# Stroya_Stompbox.net
KiCad netlist of a schematic drawn in EAGLE
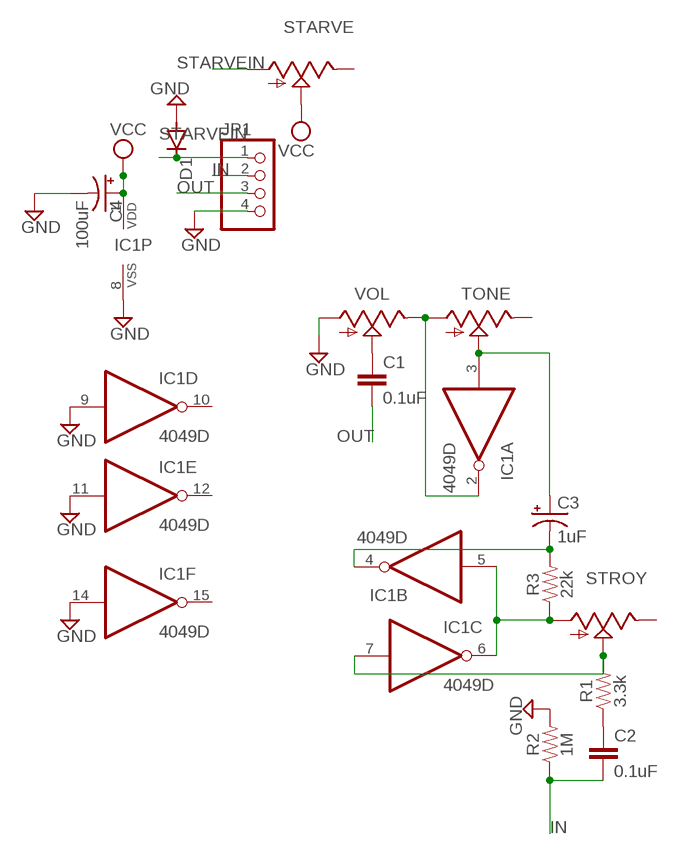
[diagram p0: schematic, sheet 1]

(export (version "E")
  (design (tool "Eeschema 10.0.6"))
  (components
    (comp (ref "C1")
      (value "0.1uF")
      (footprint "eagle-import:0603")
      (libsource (lib "eagle-import") (part "0.1UF-0603-25V-5%"))
    )
    (comp (ref "C2")
      (value "0.1uF")
      (footprint "eagle-import:0603")
      (libsource (lib "eagle-import") (part "0.1UF-0603-25V-5%"))
    )
    (comp (ref "C3")
      (value "1uF")
      (footprint "eagle-import:PAN_B_SMD+THRU")
      (libsource (lib "eagle-import") (part "CAP_SMD+THRUPAN_B"))
    )
    (comp (ref "C4")
      (value "100uF")
      (footprint "eagle-import:PAN_B_SMD+THRU")
      (libsource (lib "eagle-import") (part "CAP_SMD+THRUPAN_B"))
    )
    (comp (ref "D1")
      (value "DIODE-SOD123")
      (footprint "eagle-import:SOD123")
      (libsource (lib "eagle-import") (part "DIODE-SOD123"))
    )
    (comp (ref "IC1")
      (value "4049D")
      (footprint "eagle-import:SO16")
      (libsource (lib "eagle-import") (part "4049D"))
    )
    (comp (ref "JP1")
      (value "PINHD-1X4")
      (footprint "eagle-import:1X04")
      (libsource (lib "eagle-import") (part "PINHD-1X4"))
    )
    (comp (ref "R1")
      (value "3.3k")
      (footprint "eagle-import:0603")
      (libsource (lib "eagle-import") (part "3.3KOHM-0603-1/10W-1%"))
    )
    (comp (ref "R2")
      (value "1M")
      (footprint "eagle-import:0603")
      (libsource (lib "eagle-import") (part "1MOHM-0603-1/4W-5%"))
    )
    (comp (ref "R3")
      (value "22k")
      (footprint "eagle-import:0603")
      (libsource (lib "eagle-import") (part "22KOHM-0603-1/10W-1%"))
    )
    (comp (ref "STARVE")
      (value "9MM_SNAP-IN_POT_")
      (footprint "eagle-import:9MM_SNAP-IN_POT")
      (libsource (lib "eagle-import") (part "9MM_SNAP-IN_POT_"))
    )
    (comp (ref "STROY")
      (value "9MM_SNAP-IN_POT_")
      (footprint "eagle-import:9MM_SNAP-IN_POT")
      (libsource (lib "eagle-import") (part "9MM_SNAP-IN_POT_"))
    )
    (comp (ref "TONE")
      (value "9MM_SNAP-IN_POT_")
      (footprint "eagle-import:9MM_SNAP-IN_POT")
      (libsource (lib "eagle-import") (part "9MM_SNAP-IN_POT_"))
    )
    (comp (ref "VOL")
      (value "9MM_SNAP-IN_POT_")
      (footprint "eagle-import:9MM_SNAP-IN_POT")
      (libsource (lib "eagle-import") (part "9MM_SNAP-IN_POT_"))
    )
  )
  (nets
    (net (code "1") (name "/IN") (class "Default")
      (node (ref "C2") (pin "2") (pinfunction "2_2") (pintype "passive"))
      (node (ref "JP1") (pin "2") (pinfunction "2_2") (pintype "passive"))
      (node (ref "R2") (pin "1") (pinfunction "1_1") (pintype "passive"))
    )
    (net (code "2") (name "/OUT") (class "Default")
      (node (ref "C1") (pin "2") (pinfunction "2_2") (pintype "passive"))
      (node (ref "JP1") (pin "3") (pinfunction "3_3") (pintype "passive"))
    )
    (net (code "3") (name "/STARVEIN") (class "Default")
      (node (ref "D1") (pin "C") (pinfunction "C_C") (pintype "passive"))
      (node (ref "JP1") (pin "1") (pinfunction "1_1") (pintype "passive"))
      (node (ref "STARVE") (pin "1") (pinfunction "A_1") (pintype "passive"))
    )
    (net (code "4") (name "GND") (class "Default")
      (node (ref "C4") (pin "-") (pinfunction "-_-") (pintype "passive"))
      (node (ref "C4") (pin "--") (pinfunction "-_--") (pintype "passive"))
      (node (ref "D1") (pin "A") (pinfunction "A_A") (pintype "passive"))
      (node (ref "IC1") (pin "11") (pinfunction "I_11") (pintype "input"))
      (node (ref "IC1") (pin "14") (pinfunction "I_14") (pintype "input"))
      (node (ref "IC1") (pin "8") (pinfunction "VSS_8") (pintype "power_in"))
      (node (ref "IC1") (pin "9") (pinfunction "I_9") (pintype "input"))
      (node (ref "JP1") (pin "4") (pinfunction "4_4") (pintype "passive"))
      (node (ref "R2") (pin "2") (pinfunction "2_2") (pintype "passive"))
      (node (ref "VOL") (pin "1") (pinfunction "A_1") (pintype "passive"))
    )
    (net (code "5") (name "Net-(C2-Pad1)") (class "Default")
      (node (ref "C2") (pin "1") (pinfunction "1_1") (pintype "passive"))
      (node (ref "R1") (pin "1") (pinfunction "1_1") (pintype "passive"))
    )
    (net (code "6") (name "Net-(IC1A-I)") (class "Default")
      (node (ref "C3") (pin "+") (pinfunction "+_+") (pintype "passive"))
      (node (ref "C3") (pin "++") (pinfunction "+_++") (pintype "passive"))
      (node (ref "IC1") (pin "3") (pinfunction "I_3") (pintype "input"))
      (node (ref "TONE") (pin "2") (pinfunction "S_2") (pintype "passive"))
    )
    (net (code "7") (name "Net-(IC1A-O)") (class "Default")
      (node (ref "IC1") (pin "2") (pinfunction "O_2") (pintype "output"))
      (node (ref "TONE") (pin "1") (pinfunction "A_1") (pintype "passive"))
      (node (ref "VOL") (pin "3") (pinfunction "E_3") (pintype "passive"))
    )
    (net (code "8") (name "Net-(IC1B-I)") (class "Default")
      (node (ref "IC1") (pin "5") (pinfunction "I_5") (pintype "input"))
      (node (ref "IC1") (pin "6") (pinfunction "O_6") (pintype "output"))
      (node (ref "R3") (pin "1") (pinfunction "1_1") (pintype "passive"))
      (node (ref "STROY") (pin "1") (pinfunction "A_1") (pintype "passive"))
    )
    (net (code "9") (name "Net-(IC1B-O)") (class "Default")
      (node (ref "C3") (pin "-") (pinfunction "-_-") (pintype "passive"))
      (node (ref "C3") (pin "--") (pinfunction "-_--") (pintype "passive"))
      (node (ref "IC1") (pin "4") (pinfunction "O_4") (pintype "output"))
      (node (ref "R3") (pin "2") (pinfunction "2_2") (pintype "passive"))
    )
    (net (code "10") (name "Net-(IC1C-I)") (class "Default")
      (node (ref "IC1") (pin "7") (pinfunction "I_7") (pintype "input"))
      (node (ref "R1") (pin "2") (pinfunction "2_2") (pintype "passive"))
      (node (ref "STROY") (pin "2") (pinfunction "S_2") (pintype "passive"))
    )
    (net (code "11") (name "Net-(VOL-S)") (class "Default")
      (node (ref "C1") (pin "1") (pinfunction "1_1") (pintype "passive"))
      (node (ref "VOL") (pin "2") (pinfunction "S_2") (pintype "passive"))
    )
    (net (code "12") (name "VCC") (class "Default")
      (node (ref "C4") (pin "+") (pinfunction "+_+") (pintype "passive"))
      (node (ref "C4") (pin "++") (pinfunction "+_++") (pintype "passive"))
      (node (ref "IC1") (pin "1") (pinfunction "VDD_1") (pintype "power_in"))
      (node (ref "STARVE") (pin "2") (pinfunction "S_2") (pintype "passive"))
    )
    (net (code "13") (name "unconnected-(IC1D-O-Pad10)") (class "Default")
      (node (ref "IC1") (pin "10") (pinfunction "O_10") (pintype "output"))
    )
    (net (code "14") (name "unconnected-(IC1E-O-Pad12)") (class "Default")
      (node (ref "IC1") (pin "12") (pinfunction "O_12") (pintype "output"))
    )
    (net (code "15") (name "unconnected-(IC1F-O-Pad15)") (class "Default")
      (node (ref "IC1") (pin "15") (pinfunction "O_15") (pintype "output"))
    )
    (net (code "16") (name "unconnected-(STARVE-E-Pad3)") (class "Default")
      (node (ref "STARVE") (pin "3") (pinfunction "E_3") (pintype "passive"))
    )
    (net (code "17") (name "unconnected-(STROY-E-Pad3)") (class "Default")
      (node (ref "STROY") (pin "3") (pinfunction "E_3") (pintype "passive"))
    )
    (net (code "18") (name "unconnected-(TONE-E-Pad3)") (class "Default")
      (node (ref "TONE") (pin "3") (pinfunction "E_3") (pintype "passive"))
    )
  )
)
